# Power_P3V3.net
KiCad netlist of a schematic drawn in Altium Designer
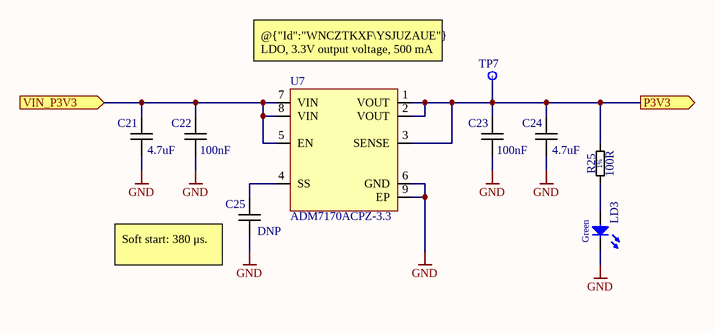
[diagram p0: Power_P3V3.SchDoc]

(export (version "E")
  (design (tool "Eeschema 10.0.6"))
  (components
    (comp (ref "C21")
      (value "4.7uF")
      (footprint "CAPC0603X90N")
      (description "Non-polarised capacitor")
      (fields (field (name "MANUFACTURER PART NUMBER") "GRM188Z71C475KE21D"))
      (libsource (lib "Capacitors") (part "Capacitor - non polarized"))
    )
    (comp (ref "C22")
      (value "100nF")
      (footprint "CAPC0603X90N")
      (description "Non-polarised capacitor")
      (fields (field (name "MANUFACTURER PART NUMBER") "VJ0603Y104KXJCW1BC"))
      (libsource (lib "Capacitors") (part "Capacitor - non polarized"))
    )
    (comp (ref "C23")
      (value "100nF")
      (footprint "CAPC0603X90N")
      (description "Non-polarised capacitor")
      (fields (field (name "MANUFACTURER PART NUMBER") "VJ0603Y104KXJCW1BC"))
      (libsource (lib "Capacitors") (part "Capacitor - non polarized"))
    )
    (comp (ref "C24")
      (value "4.7uF")
      (footprint "CAPC0603X90N")
      (description "Non-polarised capacitor")
      (fields (field (name "MANUFACTURER PART NUMBER") "GRM188Z71C475KE21D"))
      (libsource (lib "Capacitors") (part "Capacitor - non polarized"))
    )
    (comp (ref "C25")
      (value "DNP")
      (footprint "CAPC0603X90N")
      (description "Non-polarised capacitor")
      (fields (field (name "MANUFACTURER PART NUMBER") "UNDEFINED"))
      (libsource (lib "Capacitors") (part "Capacitor - non polarized"))
    )
    (comp (ref "LD3")
      (value "Green")
      (footprint "LED_0603X60N")
      (description "SMD mono-color Chip LED, Green, 0603")
      (fields (field (name "MANUFACTURER PART NUMBER") "HSME-C191"))
      (libsource (lib "ICs_and_Semiconductors") (part "LED 1C 2A"))
    )
    (comp (ref "R25")
      (value "100R")
      (footprint "RESC0603X60N")
      (description "General Purpose Thick Film Chip Resistor")
      (fields (field (name "MANUFACTURER PART NUMBER") "0603SAF1000T5E") (field (name "TOLERANCE") "1%"))
      (libsource (lib "Resistors") (part "Resistor - 1%"))
    )
    (comp (ref "TP7")
      (value "TestPoint")
      (footprint "TESTPOINT_SMD_C1P27MM")
      (description "1.27mm diameter SMD Test Point Area")
      (libsource (lib "Mechanical_and_PCB_Features") (part "Test Point"))
    )
    (comp (ref "U7")
      (value "ADM7170ACPZ-3.3")
      (footprint "LFCSP50P300X300X80-9N-D")
      (description "3.3V, 500 mA, Ultralow Noise, High PSRR,Fast Transient Response CMOS LDO, FIXED, LFCSP-8")
      (fields (field (name "MANUFACTURER PART NUMBER") "ADM7170ACPZ-3.3-R7"))
      (libsource (lib "ICs_and_Semiconductors") (part "ADM7170ACPZ-3.3"))
    )
  )
  (nets
    (net (code "1") (name "/P3V3") (class "Default")
      (node (ref "C23") (pin "1") (pinfunction "1_1") (pintype "passive"))
      (node (ref "C24") (pin "1") (pinfunction "1_1") (pintype "passive"))
      (node (ref "R25") (pin "2") (pinfunction "2_2") (pintype "passive"))
      (node (ref "TP7") (pin "1") (pinfunction "1_1") (pintype "passive"))
      (node (ref "U7") (pin "1") (pinfunction "VOUT_1") (pintype "passive"))
      (node (ref "U7") (pin "2") (pinfunction "VOUT_2") (pintype "passive"))
      (node (ref "U7") (pin "3") (pinfunction "SENSE_3") (pintype "passive"))
    )
    (net (code "2") (name "/VIN_P3V3") (class "Default")
      (node (ref "C21") (pin "1") (pinfunction "1_1") (pintype "passive"))
      (node (ref "C22") (pin "1") (pinfunction "1_1") (pintype "passive"))
      (node (ref "U7") (pin "5") (pinfunction "EN_5") (pintype "passive"))
      (node (ref "U7") (pin "7") (pinfunction "VIN_7") (pintype "passive"))
      (node (ref "U7") (pin "8") (pinfunction "VIN_8") (pintype "passive"))
    )
    (net (code "3") (name "GND") (class "Default")
      (node (ref "C21") (pin "2") (pinfunction "2_2") (pintype "passive"))
      (node (ref "C22") (pin "2") (pinfunction "2_2") (pintype "passive"))
      (node (ref "C23") (pin "2") (pinfunction "2_2") (pintype "passive"))
      (node (ref "C24") (pin "2") (pinfunction "2_2") (pintype "passive"))
      (node (ref "C25") (pin "2") (pinfunction "2_2") (pintype "passive"))
      (node (ref "LD3") (pin "1") (pinfunction "C_1") (pintype "passive"))
      (node (ref "U7") (pin "6") (pinfunction "GND_6") (pintype "power_in"))
      (node (ref "U7") (pin "9") (pinfunction "EP_9") (pintype "passive"))
    )
    (net (code "4") (name "Net-(LD3-A)") (class "Default")
      (node (ref "LD3") (pin "2") (pinfunction "A_2") (pintype "passive"))
      (node (ref "R25") (pin "1") (pinfunction "1_1") (pintype "passive"))
    )
    (net (code "5") (name "Net-(U7-SS)") (class "Default")
      (node (ref "C25") (pin "1") (pinfunction "1_1") (pintype "passive"))
      (node (ref "U7") (pin "4") (pinfunction "SS_4") (pintype "passive"))
    )
  )
)
